# Camera.net
KiCad netlist of a schematic drawn in Altium Designer
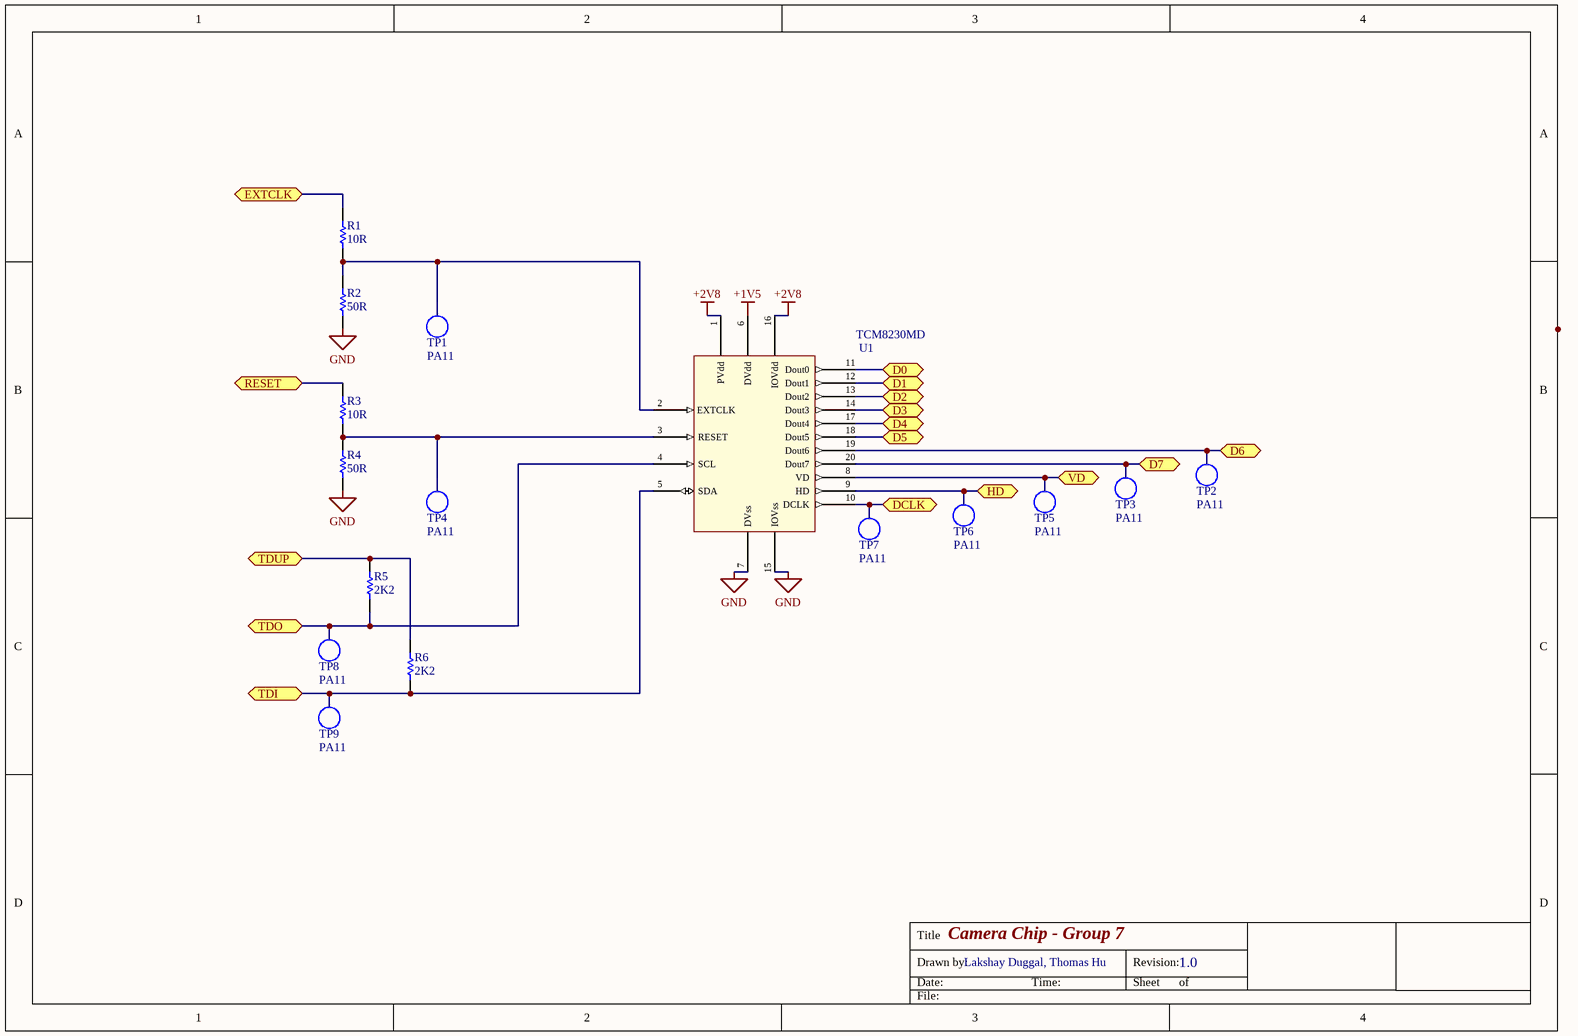
[diagram p0: Camera.SchDoc]

(export (version "E")
  (design (tool "Eeschema 10.0.6"))
  (components
    (comp (ref "R1")
      (value "10R")
      (footprint "ECE Components_16_2:RESC1608L")
      (description "RES 2.2K OHM 1/10W 5% 0603 SMD")
      (libsource (lib "ECE Components_15_7") (part "RS_2K2"))
    )
    (comp (ref "R2")
      (value "50R")
      (footprint "ECE Components_16_2:RESC1608L")
      (description "RES 2.2K OHM 1/10W 5% 0603 SMD")
      (libsource (lib "ECE Components_15_7") (part "RS_2K2"))
    )
    (comp (ref "R3")
      (value "10R")
      (footprint "ECE Components_16_2:RESC1608L")
      (description "RES 2.2K OHM 1/10W 5% 0603 SMD")
      (libsource (lib "ECE Components_15_7") (part "RS_2K2"))
    )
    (comp (ref "R4")
      (value "50R")
      (footprint "ECE Components_16_2:RESC1608L")
      (description "RES 2.2K OHM 1/10W 5% 0603 SMD")
      (libsource (lib "ECE Components_15_7") (part "RS_2K2"))
    )
    (comp (ref "R5")
      (value "2K2")
      (footprint "ECE Components_16_2:RESC1608L")
      (description "RES 2.2K OHM 1/10W 5% 0603 SMD")
      (libsource (lib "ECE Components_15_7") (part "RS_2K2"))
    )
    (comp (ref "R6")
      (value "2K2")
      (footprint "ECE Components_16_2:RESC1608L")
      (description "RES 2.2K OHM 1/10W 5% 0603 SMD")
      (libsource (lib "ECE Components_15_7") (part "RS_2K2"))
    )
    (comp (ref "TP1")
      (value "PA11")
      (footprint "ECE Components_16_2:TP_0805")
      (description "Test Point 2.0X0.9X1.2mm SMD")
      (fields
        (field (name "MANUFACTURER") "TE Connectivity AMP Connectors")
        (field (name "MANUFACTURER PART NUMBER") "1625854-2")
      )
      (libsource (lib "ECE Components_15_7") (part "TP_0805"))
    )
    (comp (ref "TP2")
      (value "PA11")
      (footprint "ECE Components_16_2:TP_0805")
      (description "Test Point 2.0X0.9X1.2mm SMD")
      (fields
        (field (name "MANUFACTURER") "TE Connectivity AMP Connectors")
        (field (name "MANUFACTURER PART NUMBER") "1625854-2")
      )
      (libsource (lib "ECE Components_15_7") (part "TP_0805"))
    )
    (comp (ref "TP3")
      (value "PA11")
      (footprint "ECE Components_16_2:TP_0805")
      (description "Test Point 2.0X0.9X1.2mm SMD")
      (fields
        (field (name "MANUFACTURER") "TE Connectivity AMP Connectors")
        (field (name "MANUFACTURER PART NUMBER") "1625854-2")
      )
      (libsource (lib "ECE Components_15_7") (part "TP_0805"))
    )
    (comp (ref "TP4")
      (value "PA11")
      (footprint "ECE Components_16_2:TP_0805")
      (description "Test Point 2.0X0.9X1.2mm SMD")
      (fields
        (field (name "MANUFACTURER") "TE Connectivity AMP Connectors")
        (field (name "MANUFACTURER PART NUMBER") "1625854-2")
      )
      (libsource (lib "ECE Components_15_7") (part "TP_0805"))
    )
    (comp (ref "TP5")
      (value "PA11")
      (footprint "ECE Components_16_2:TP_0805")
      (description "Test Point 2.0X0.9X1.2mm SMD")
      (fields
        (field (name "MANUFACTURER") "TE Connectivity AMP Connectors")
        (field (name "MANUFACTURER PART NUMBER") "1625854-2")
      )
      (libsource (lib "ECE Components_15_7") (part "TP_0805"))
    )
    (comp (ref "TP6")
      (value "PA11")
      (footprint "ECE Components_16_2:TP_0805")
      (description "Test Point 2.0X0.9X1.2mm SMD")
      (fields
        (field (name "MANUFACTURER") "TE Connectivity AMP Connectors")
        (field (name "MANUFACTURER PART NUMBER") "1625854-2")
      )
      (libsource (lib "ECE Components_15_7") (part "TP_0805"))
    )
    (comp (ref "TP7")
      (value "PA11")
      (footprint "ECE Components_16_2:TP_0805")
      (description "Test Point 2.0X0.9X1.2mm SMD")
      (fields
        (field (name "MANUFACTURER") "TE Connectivity AMP Connectors")
        (field (name "MANUFACTURER PART NUMBER") "1625854-2")
      )
      (libsource (lib "ECE Components_15_7") (part "TP_0805"))
    )
    (comp (ref "TP8")
      (value "PA11")
      (footprint "ECE Components_16_2:TP_0805")
      (description "Test Point 2.0X0.9X1.2mm SMD")
      (fields
        (field (name "MANUFACTURER") "TE Connectivity AMP Connectors")
        (field (name "MANUFACTURER PART NUMBER") "1625854-2")
      )
      (libsource (lib "ECE Components_15_7") (part "TP_0805"))
    )
    (comp (ref "TP9")
      (value "PA11")
      (footprint "ECE Components_16_2:TP_0805")
      (description "Test Point 2.0X0.9X1.2mm SMD")
      (fields
        (field (name "MANUFACTURER") "TE Connectivity AMP Connectors")
        (field (name "MANUFACTURER PART NUMBER") "1625854-2")
      )
      (libsource (lib "ECE Components_15_7") (part "TP_0805"))
    )
    (comp (ref "U1")
      (value "TCM8230MD")
      (footprint "ENEL461_15.4:TCM8230MD")
      (description "Toshiba I2C Camera")
      (fields (field (name "MANUFACTURER") "Toshiba"))
      (libsource (lib "ENEL461_15.3") (part "TCM8230MD"))
    )
  )
  (nets
    (net (code "1") (name "+1V5") (class "Default")
      (node (ref "U1") (pin "6") (pinfunction "DVdd_6") (pintype "power_in"))
    )
    (net (code "2") (name "+2V8") (class "Default")
      (node (ref "U1") (pin "1") (pinfunction "PVdd_1") (pintype "power_in"))
      (node (ref "U1") (pin "16") (pinfunction "IOVdd_16") (pintype "power_in"))
    )
    (net (code "3") (name "/D0") (class "Default")
      (node (ref "U1") (pin "11") (pinfunction "Dout0_11") (pintype "output"))
    )
    (net (code "4") (name "/D1") (class "Default")
      (node (ref "U1") (pin "12") (pinfunction "Dout1_12") (pintype "output"))
    )
    (net (code "5") (name "/D2") (class "Default")
      (node (ref "U1") (pin "13") (pinfunction "Dout2_13") (pintype "output"))
    )
    (net (code "6") (name "/D3") (class "Default")
      (node (ref "U1") (pin "14") (pinfunction "Dout3_14") (pintype "output"))
    )
    (net (code "7") (name "/D4") (class "Default")
      (node (ref "U1") (pin "17") (pinfunction "Dout4_17") (pintype "output"))
    )
    (net (code "8") (name "/D5") (class "Default")
      (node (ref "U1") (pin "18") (pinfunction "Dout5_18") (pintype "output"))
    )
    (net (code "9") (name "/D6") (class "Default")
      (node (ref "TP2") (pin "1") (pinfunction "TP_1") (pintype "passive"))
      (node (ref "U1") (pin "19") (pinfunction "Dout6_19") (pintype "output"))
    )
    (net (code "10") (name "/D7") (class "Default")
      (node (ref "TP3") (pin "1") (pinfunction "TP_1") (pintype "passive"))
      (node (ref "U1") (pin "20") (pinfunction "Dout7_20") (pintype "output"))
    )
    (net (code "11") (name "/DCLK") (class "Default")
      (node (ref "TP7") (pin "1") (pinfunction "TP_1") (pintype "passive"))
      (node (ref "U1") (pin "10") (pinfunction "DCLK_10") (pintype "output"))
    )
    (net (code "12") (name "/EXTCLK") (class "Default")
      (node (ref "R1") (pin "2") (pinfunction "2_2") (pintype "passive"))
    )
    (net (code "13") (name "/HD") (class "Default")
      (node (ref "TP6") (pin "1") (pinfunction "TP_1") (pintype "passive"))
      (node (ref "U1") (pin "9") (pinfunction "HD_9") (pintype "output"))
    )
    (net (code "14") (name "/RESET") (class "Default")
      (node (ref "R3") (pin "2") (pinfunction "2_2") (pintype "passive"))
    )
    (net (code "15") (name "/TDI") (class "Default")
      (node (ref "R6") (pin "1") (pinfunction "1_1") (pintype "passive"))
      (node (ref "TP9") (pin "1") (pinfunction "TP_1") (pintype "passive"))
      (node (ref "U1") (pin "5") (pinfunction "SDA_5") (pintype "bidirectional"))
    )
    (net (code "16") (name "/TDO") (class "Default")
      (node (ref "R5") (pin "1") (pinfunction "1_1") (pintype "passive"))
      (node (ref "TP8") (pin "1") (pinfunction "TP_1") (pintype "passive"))
      (node (ref "U1") (pin "4") (pinfunction "SCL_4") (pintype "input"))
    )
    (net (code "17") (name "/TDUP") (class "Default")
      (node (ref "R5") (pin "2") (pinfunction "2_2") (pintype "passive"))
      (node (ref "R6") (pin "2") (pinfunction "2_2") (pintype "passive"))
    )
    (net (code "18") (name "/VD") (class "Default")
      (node (ref "TP5") (pin "1") (pinfunction "TP_1") (pintype "passive"))
      (node (ref "U1") (pin "8") (pinfunction "VD_8") (pintype "output"))
    )
    (net (code "19") (name "GND") (class "Default")
      (node (ref "R2") (pin "1") (pinfunction "1_1") (pintype "passive"))
      (node (ref "R4") (pin "1") (pinfunction "1_1") (pintype "passive"))
      (node (ref "U1") (pin "15") (pinfunction "IOVss_15") (pintype "power_in"))
      (node (ref "U1") (pin "7") (pinfunction "DVss_7") (pintype "power_in"))
    )
    (net (code "20") (name "Net-(TP1-TP)") (class "Default")
      (node (ref "R1") (pin "1") (pinfunction "1_1") (pintype "passive"))
      (node (ref "R2") (pin "2") (pinfunction "2_2") (pintype "passive"))
      (node (ref "TP1") (pin "1") (pinfunction "TP_1") (pintype "passive"))
      (node (ref "U1") (pin "2") (pinfunction "EXTCLK_2") (pintype "input"))
    )
    (net (code "21") (name "Net-(TP4-TP)") (class "Default")
      (node (ref "R3") (pin "1") (pinfunction "1_1") (pintype "passive"))
      (node (ref "R4") (pin "2") (pinfunction "2_2") (pintype "passive"))
      (node (ref "TP4") (pin "1") (pinfunction "TP_1") (pintype "passive"))
      (node (ref "U1") (pin "3") (pinfunction "RESET_3") (pintype "input"))
    )
  )
)
